# encoder.net
KiCad netlist of a schematic drawn in Altium Designer
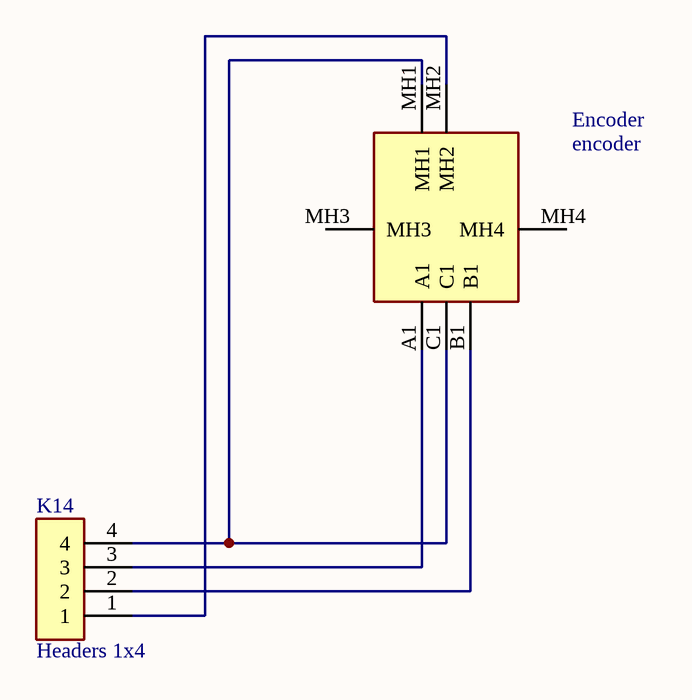
[diagram p0: encoder.SchDoc]

(export (version "E")
  (design (tool "Eeschema 10.0.6"))
  (components
    (comp (ref "Encoder")
      (value "encoder")
      (footprint "encoder")
      (description "Undefined or Miscellaneous")
      (fields
        (field (name "MOUSER2 PART NUMBER") "318-ENC130175F-12PS")
        (field (name "MANUFACTURER_PART_NUMBER") "RE130F-41-175F-12P")
      )
      (libsource (lib "project-2022") (part "encoder"))
    )
    (comp (ref "K14")
      (value "Headers 1x4")
      (footprint "Headers 1x4")
      (description "Connector")
      (fields (field (name "MANUFACTURER_PART_NUMBER") "2-826646-0"))
      (libsource (lib "project-2022") (part "Headers 1x4"))
    )
  )
  (nets
    (net (code "1") (name "Net-(Encoder-PadA1)") (class "Default")
      (node (ref "Encoder") (pin "A1") (pinfunction "A1_A1") (pintype "passive"))
      (node (ref "K14") (pin "3") (pinfunction "3_3") (pintype "passive"))
    )
    (net (code "2") (name "Net-(Encoder-PadB1)") (class "Default")
      (node (ref "Encoder") (pin "B1") (pinfunction "B1_B1") (pintype "passive"))
      (node (ref "K14") (pin "2") (pinfunction "2_2") (pintype "passive"))
    )
    (net (code "3") (name "Net-(Encoder-PadC1)") (class "Default")
      (node (ref "Encoder") (pin "C1") (pinfunction "C1_C1") (pintype "passive"))
      (node (ref "Encoder") (pin "MH1") (pinfunction "MH1_MH1") (pintype "passive"))
      (node (ref "K14") (pin "4") (pinfunction "4_4") (pintype "passive"))
    )
    (net (code "4") (name "Net-(Encoder-PadMH2)") (class "Default")
      (node (ref "Encoder") (pin "MH2") (pinfunction "MH2_MH2") (pintype "passive"))
      (node (ref "K14") (pin "1") (pinfunction "1_1") (pintype "passive"))
    )
    (net (code "5") (name "unconnected-(Encoder-PadMH3)") (class "Default")
      (node (ref "Encoder") (pin "MH3") (pinfunction "MH3_MH3") (pintype "passive"))
    )
    (net (code "6") (name "unconnected-(Encoder-PadMH4)") (class "Default")
      (node (ref "Encoder") (pin "MH4") (pinfunction "MH4_MH4") (pintype "passive"))
    )
  )
)
